# uStar.net
KiCad netlist of a schematic drawn in EAGLE
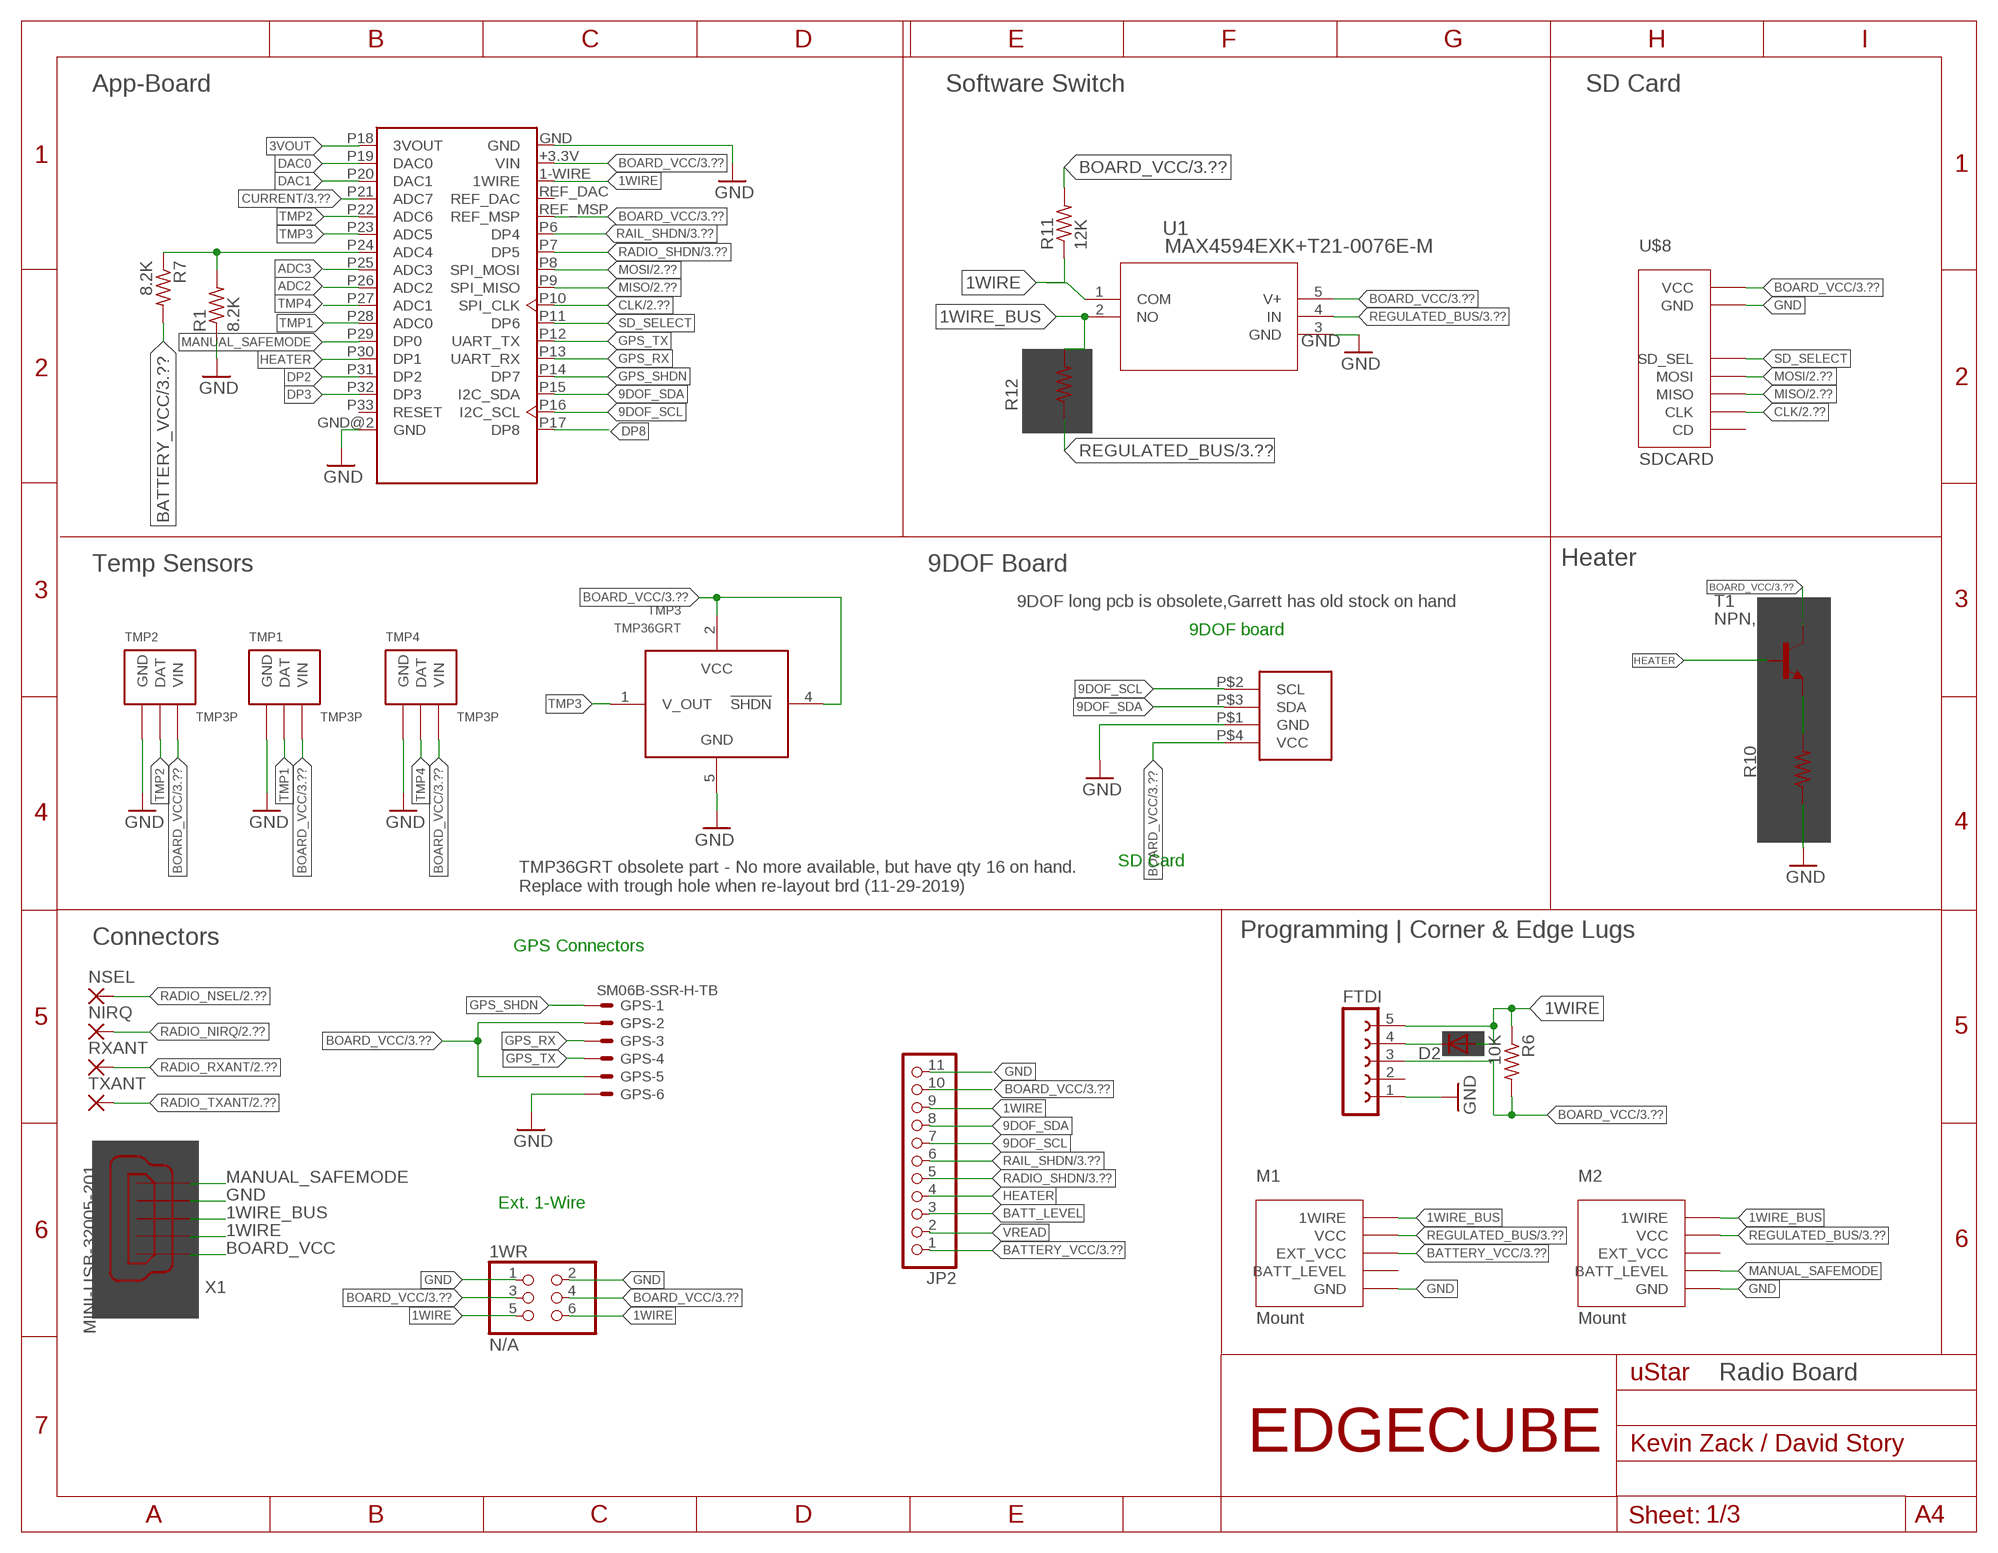
[diagram p0: schematic, sheet 1]
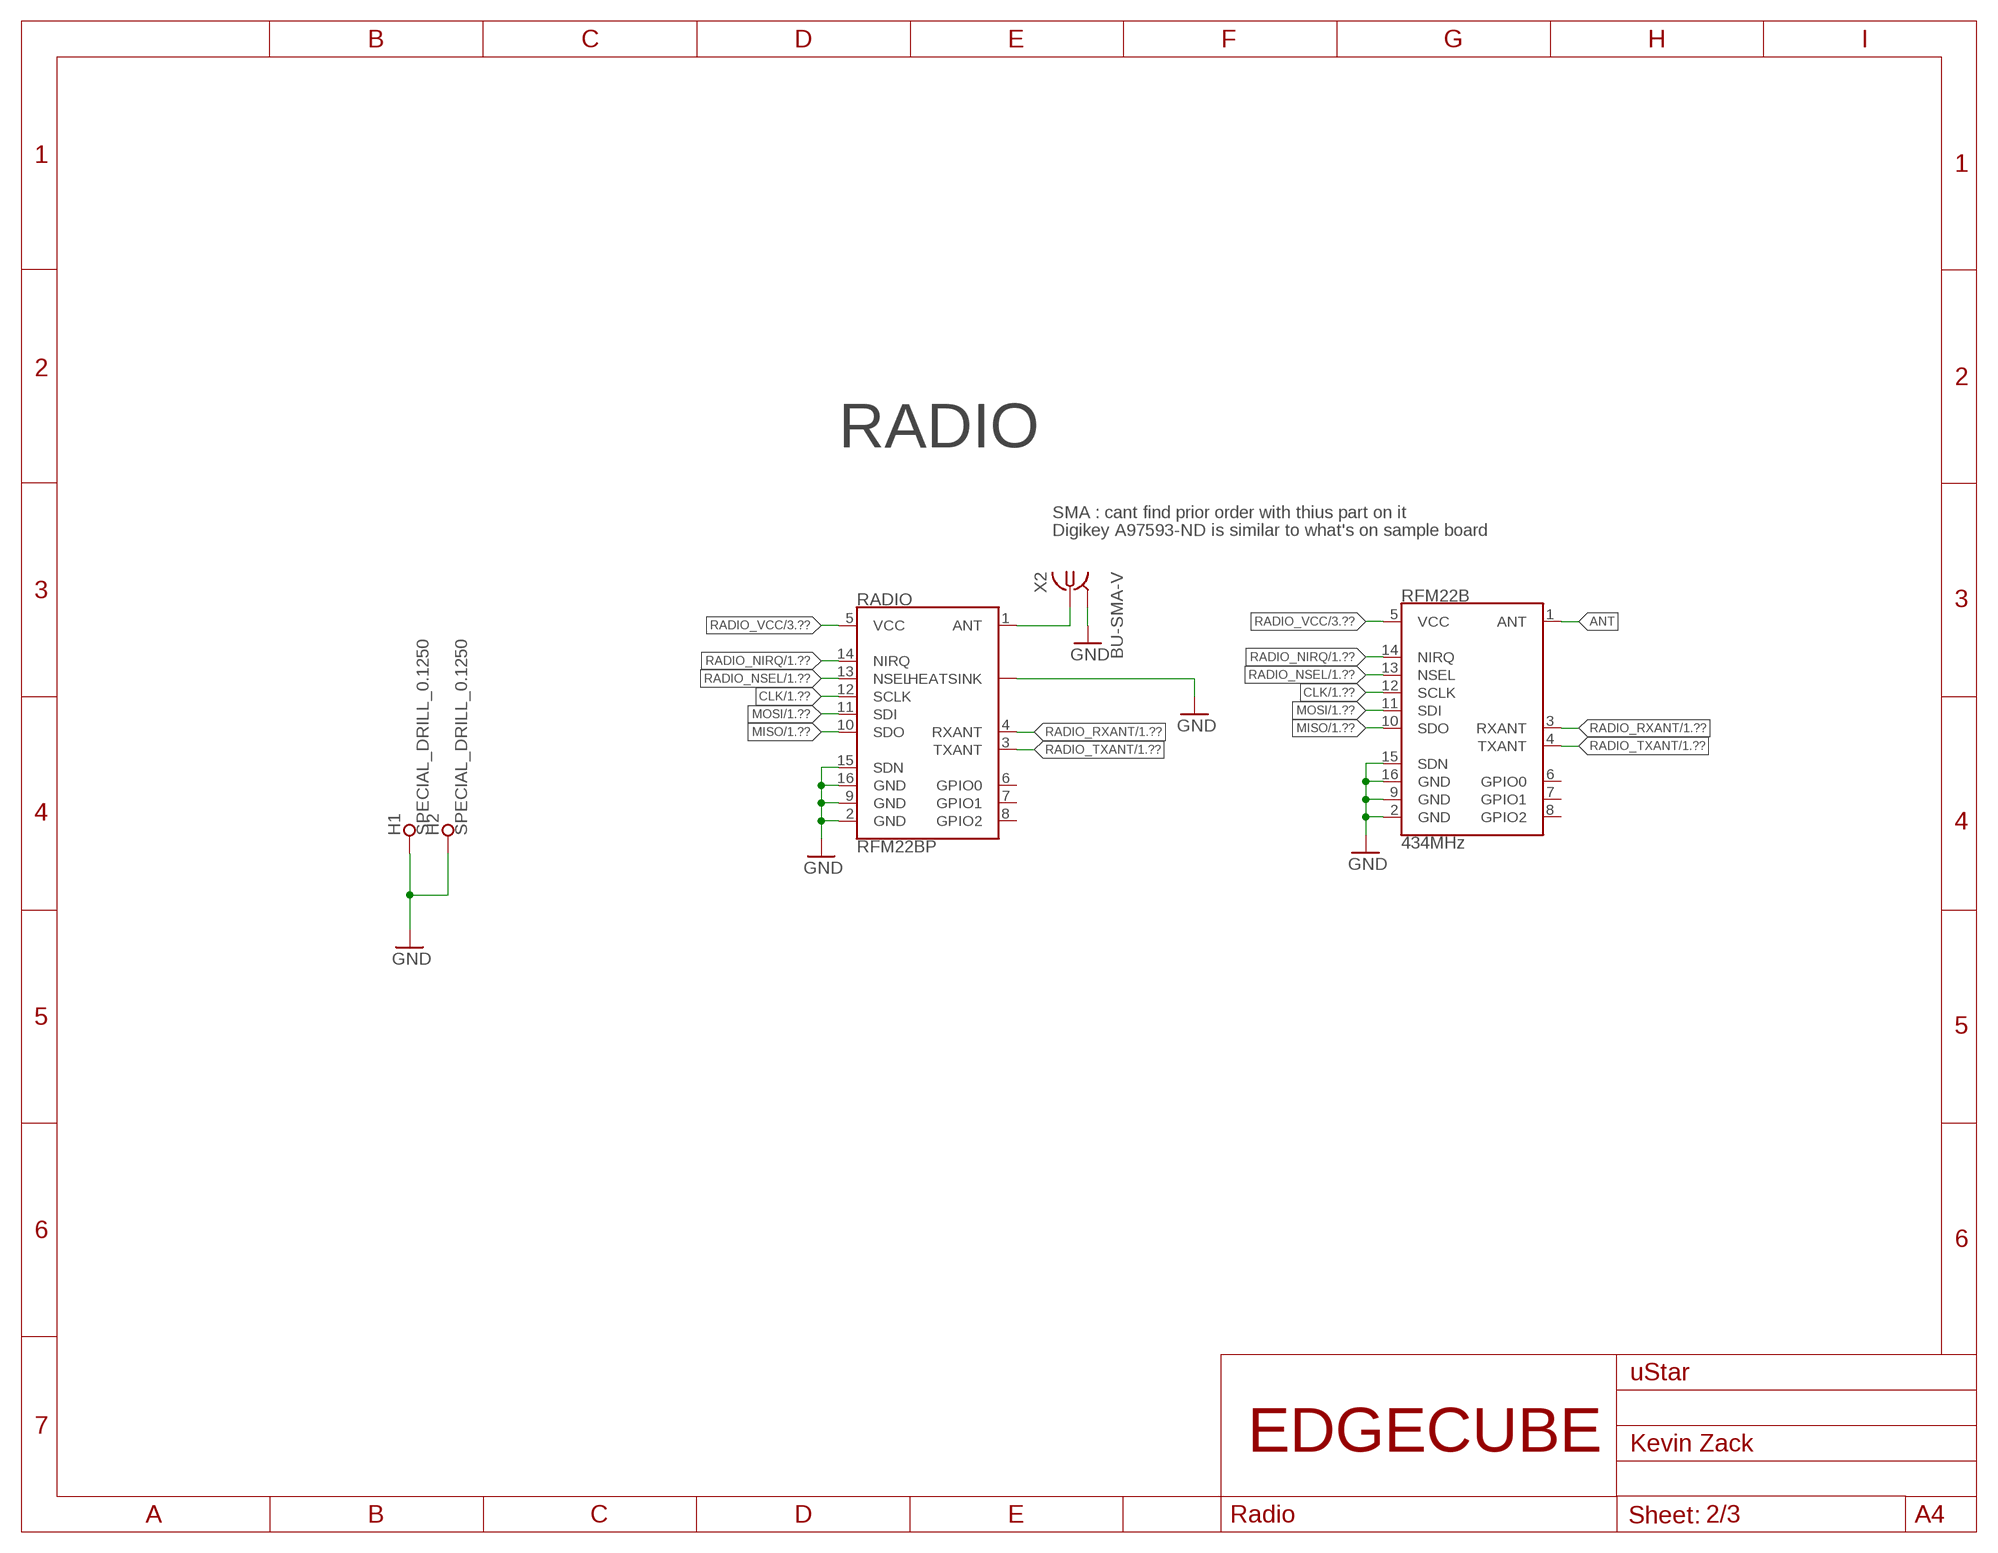
[diagram p1: schematic, sheet 2]
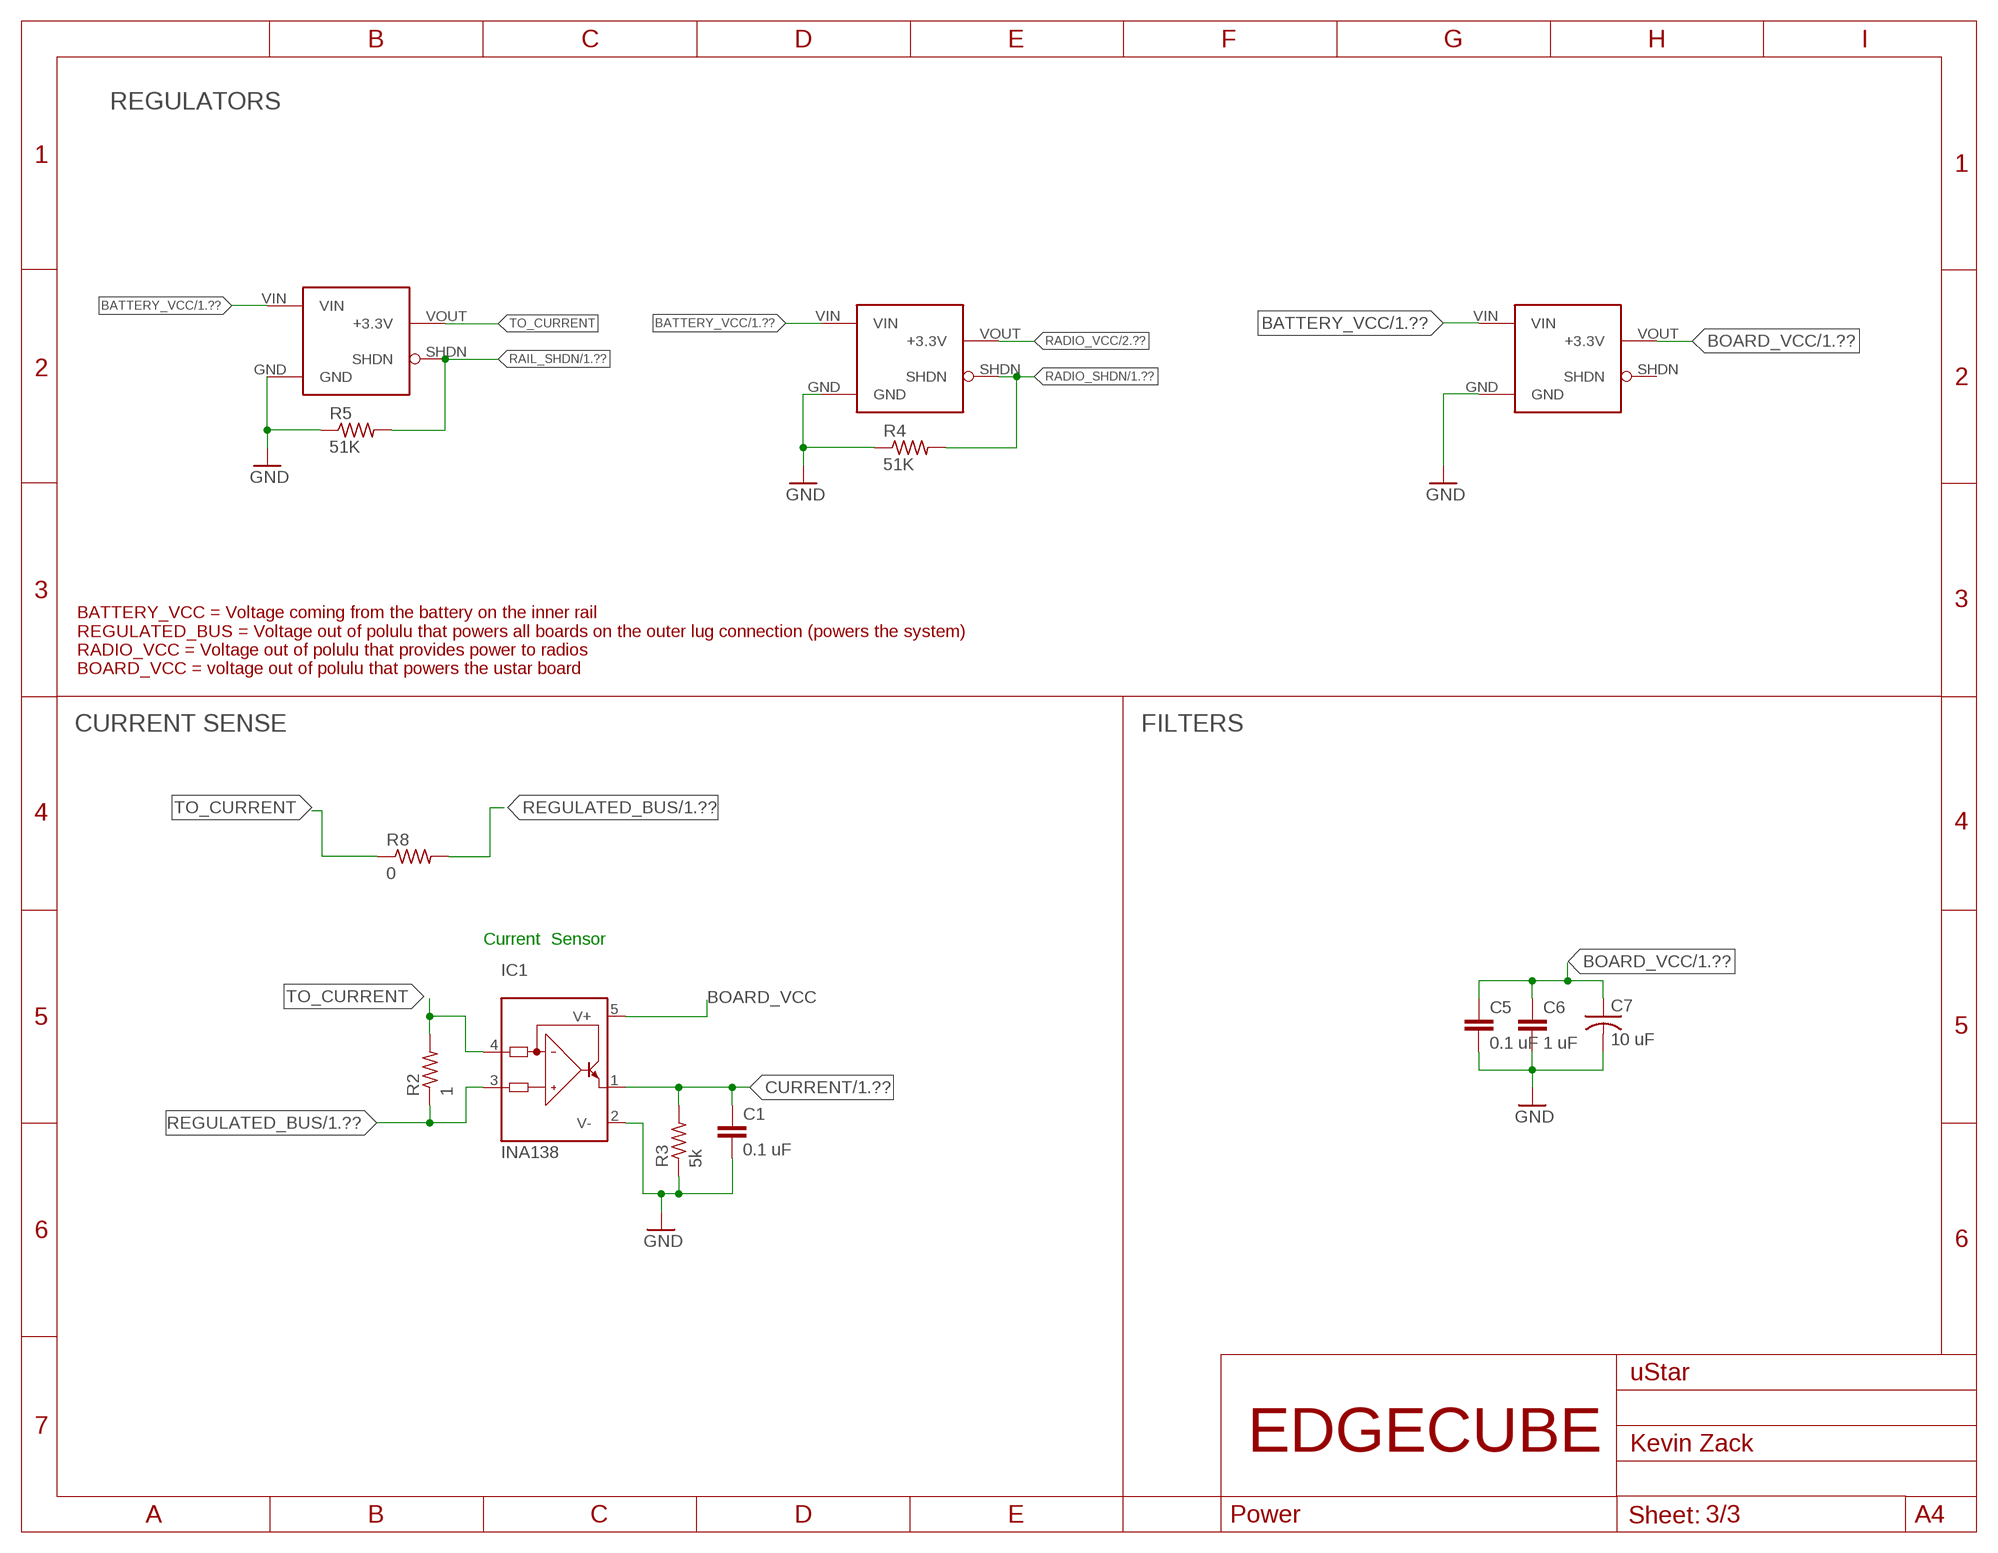
[diagram p2: schematic, sheet 3]

(export (version "E")
  (design (tool "Eeschema 10.0.6"))
  (components
    (comp (ref "C1")
      (value "0.1 uF")
      (footprint "eagle-import:C0603")
      (fields (field (name "MANUFACTURER") "AVX Corperation") (field (name "VOLTAGE") "50 V"))
      (libsource (lib "eagle-import") (part "CAP-0603-0.1UF"))
    )
    (comp (ref "C5")
      (value "0.1 uF")
      (footprint "eagle-import:C0603")
      (fields (field (name "MANUFACTURER") "AVX Corperation") (field (name "VOLTAGE") "50 V"))
      (libsource (lib "eagle-import") (part "CAP-0603-0.1UF"))
    )
    (comp (ref "C6")
      (value "1 uF")
      (footprint "eagle-import:C0603")
      (fields (field (name "MANUFACTURER") "Taiyo Yuden") (field (name "VOLTAGE") "25 V"))
      (libsource (lib "eagle-import") (part "CAP-0603-1UF"))
    )
    (comp (ref "C7")
      (value "10 uF")
      (footprint "eagle-import:C0805_POL")
      (fields (field (name "VOLTAGE") "10 V"))
      (libsource (lib "eagle-import") (part "CAP-0805-10UF-TANT"))
    )
    (comp (ref "IC1")
      (value "INA138")
      (footprint "eagle-import:SOT23-5")
      (fields (field (name "MF") "TEXAS INSTRUMENTS") (field (name "MPN") "INA138NA/250"))
      (libsource (lib "eagle-import") (part "INA138"))
    )
    (comp (ref "R2")
      (value "1")
      (footprint "eagle-import:R0603")
      (libsource (lib "eagle-import") (part "resistor_348_R-US_R0603"))
    )
    (comp (ref "R3")
      (value "5k")
      (footprint "eagle-import:R0603")
      (libsource (lib "eagle-import") (part "resistor_348_R-US_R0603"))
    )
    (comp (ref "R4")
      (value "51K")
      (footprint "eagle-import:R0603")
      (fields (field (name "MANUFACTURER") "Vishay Dale") (field (name "POWER") "0.1W"))
      (libsource (lib "eagle-import") (part "RES-0603-51K"))
    )
    (comp (ref "R5")
      (value "51K")
      (footprint "eagle-import:R0603")
      (fields (field (name "MANUFACTURER") "Vishay Dale") (field (name "POWER") "0.1W"))
      (libsource (lib "eagle-import") (part "RES-0603-51K"))
    )
    (comp (ref "R8")
      (value "0")
      (footprint "eagle-import:R1210W")
      (libsource (lib "eagle-import") (part "R-US_R1210W"))
    )
    (comp (ref "VR1")
      (value "S7V8F3_VOLT_REG-3V3_1AHORZ-DOWN")
      (footprint "eagle-import:S7V_DOWN")
      (libsource (lib "eagle-import") (part "S7V8F3_VOLT_REG-3V3_1AHORZ-DOWN"))
    )
    (comp (ref "VR2")
      (value "S7V8F3_VOLT_REG-3V3_1AHORZ-DOWN")
      (footprint "eagle-import:S7V_DOWN")
      (libsource (lib "eagle-import") (part "S7V8F3_VOLT_REG-3V3_1AHORZ-DOWN"))
    )
    (comp (ref "VR3")
      (value "S7V8F3_VOLT_REG-3V3_1AHORZ-DOWN")
      (footprint "eagle-import:S7V_DOWN")
      (libsource (lib "eagle-import") (part "S7V8F3_VOLT_REG-3V3_1AHORZ-DOWN"))
    )
    (comp (ref "1WR")
      (value "N/A")
      (footprint "eagle-import:2X03")
      (libsource (lib "eagle-import") (part "PINHD-2X3"))
    )
    (comp (ref "D2")
      (value "D-B260A")
      (footprint "eagle-import:SMA-DO214AC")
      (fields (field (name "MANUFACTURER") "Diodes Incorporated") (field (name "VOLTAGE") "60V"))
      (libsource (lib "eagle-import") (part "D-B260A"))
    )
    (comp (ref "FTDI")
      (value "FE05-1")
      (footprint "eagle-import:FE05-1")
      (libsource (lib "eagle-import") (part "FE05-1"))
    )
    (comp (ref "GPS")
      (value "SM06B-SSR-H-TB")
      (footprint "eagle-import:SM06B-SSR-H-TB")
      (libsource (lib "eagle-import") (part "SM06B-SSR-H-TB"))
    )
    (comp (ref "JP2")
      (value "PINHD-1X11")
      (footprint "eagle-import:1X11")
      (libsource (lib "eagle-import") (part "PINHD-1X11"))
    )
    (comp (ref "M1")
      (value "Mount")
      (footprint "eagle-import:4X8MOUNT")
      (libsource (lib "eagle-import") (part "4X8MOUNT"))
    )
    (comp (ref "M2")
      (value "Mount")
      (footprint "eagle-import:4X8MOUNT")
      (libsource (lib "eagle-import") (part "4X8MOUNT"))
    )
    (comp (ref "NIRQ")
      (value "1,6/0,9")
      (footprint "eagle-import:1,6_0,9")
      (libsource (lib "eagle-import") (part "1,6/0,9"))
    )
    (comp (ref "NSEL")
      (value "1,6/0,9")
      (footprint "eagle-import:1,6_0,9")
      (libsource (lib "eagle-import") (part "1,6/0,9"))
    )
    (comp (ref "PCB1")
      (value "9DOF")
      (footprint "eagle-import:9DOF")
      (libsource (lib "eagle-import") (part "9DOF"))
    )
    (comp (ref "R1")
      (value "8.2K")
      (footprint "eagle-import:R0805")
      (libsource (lib "eagle-import") (part "resistor_348_R-US_R0805"))
    )
    (comp (ref "R6")
      (value "10K")
      (footprint "eagle-import:R0603")
      (fields (field (name "MANUFACTURER") "Vishay Dale") (field (name "POWER") "0.1W"))
      (libsource (lib "eagle-import") (part "RES-0603-10K"))
    )
    (comp (ref "R7")
      (value "8.2K")
      (footprint "eagle-import:R0805")
      (libsource (lib "eagle-import") (part "resistor_348_R-US_R0805"))
    )
    (comp (ref "R10")
      (value "22")
      (footprint "eagle-import:0207_7")
      (libsource (lib "eagle-import") (part "R-US_0207/7"))
    )
    (comp (ref "R11")
      (value "12K")
      (footprint "eagle-import:R0805")
      (libsource (lib "eagle-import") (part "R-US_R0805"))
    )
    (comp (ref "R12")
      (value "NP")
      (footprint "eagle-import:R0805")
      (libsource (lib "eagle-import") (part "R-US_R0805"))
    )
    (comp (ref "RXANT")
      (value "1,6/0,9")
      (footprint "eagle-import:1,6_0,9")
      (libsource (lib "eagle-import") (part "1,6/0,9"))
    )
    (comp (ref "T1")
      (value "NPN, 0.25A")
      (footprint "eagle-import:TO92-EBC-OVAL")
      (libsource (lib "eagle-import") (part "2N2222"))
    )
    (comp (ref "TMP1")
      (value "TMP3P")
      (footprint "eagle-import:TMP3P")
      (libsource (lib "eagle-import") (part "TMP3P"))
    )
    (comp (ref "TMP2")
      (value "TMP3P")
      (footprint "eagle-import:TMP3P")
      (libsource (lib "eagle-import") (part "TMP3P"))
    )
    (comp (ref "TMP3")
      (value "TMP36GRT")
      (footprint "eagle-import:SOT-23-5")
      (fields
        (field (name "MANUFACTURER") "Analog Devices Inc.")
        (field (name "VOLTAGE") "2.7V-5.5V")
        (field (name "DIGIKEY") "obsolete")
      )
      (libsource (lib "eagle-import") (part "TMP36GRT"))
    )
    (comp (ref "TMP4")
      (value "TMP3P")
      (footprint "eagle-import:TMP3P")
      (libsource (lib "eagle-import") (part "TMP3P"))
    )
    (comp (ref "TXANT")
      (value "1,6/0,9")
      (footprint "eagle-import:1,6_0,9")
      (libsource (lib "eagle-import") (part "1,6/0,9"))
    )
    (comp (ref "U$1")
      (value "App-Board 1.2/1.3")
      (footprint "eagle-import:APPCORE_RECEIVER")
      (libsource (lib "eagle-import") (part "APP_CORE"))
    )
    (comp (ref "U$8")
      (value "SDCARD")
      (footprint "eagle-import:SDCARD")
      (libsource (lib "eagle-import") (part "SDCARD"))
    )
    (comp (ref "U1")
      (value "MAX4594EXK+T21-0076E-M")
      (footprint "eagle-import:21-0076E-M")
      (fields (field (name "MANUFACTURER_PART_NUMBER") "MAX4594EXK+T"))
      (libsource (lib "eagle-import") (part "MAX4594EXK+T21-0076E-M"))
    )
    (comp (ref "X1")
      (value "MINI-USB-32005-201")
      (footprint "eagle-import:32005-201")
      (libsource (lib "eagle-import") (part "MINI-USB-32005-201"))
    )
    (comp (ref "H1")
      (value "SPECIAL_DRILL_0.1250")
      (footprint "eagle-import:PAD_0.1250")
      (libsource (lib "eagle-import") (part "SPECIAL_DRILL_0.1250"))
    )
    (comp (ref "H2")
      (value "SPECIAL_DRILL_0.1250")
      (footprint "eagle-import:PAD_0.1250")
      (libsource (lib "eagle-import") (part "SPECIAL_DRILL_0.1250"))
    )
    (comp (ref "RADIO")
      (value "RFM22BP")
      (footprint "eagle-import:RFM22BP")
      (fields (field (name "MANUFACTURER") "HOPERF Electronic"))
      (libsource (lib "eagle-import") (part "RFM22BP"))
    )
    (comp (ref "RFM22B")
      (value "434MHz")
      (footprint "eagle-import:RFM22-XXX-S2")
      (libsource (lib "eagle-import") (part "RFM22434MHZ"))
    )
    (comp (ref "X2")
      (value "BU-SMA-V")
      (footprint "eagle-import:BU-SMA-V")
      (libsource (lib "eagle-import") (part "BU-SMA-V"))
    )
  )
  (nets
    (net (code "1") (name "1WIRE") (class "Default")
      (node (ref "1WR") (pin "5") (pinfunction "5_5") (pintype "passive"))
      (node (ref "1WR") (pin "6") (pinfunction "6_6") (pintype "passive"))
      (node (ref "D2") (pin "A") (pinfunction "A_A") (pintype "passive"))
      (node (ref "FTDI") (pin "5") (pinfunction "5_5") (pintype "passive"))
      (node (ref "JP2") (pin "9") (pinfunction "9_9") (pintype "passive"))
      (node (ref "R11") (pin "1") (pinfunction "1_1") (pintype "passive"))
      (node (ref "R6") (pin "1") (pinfunction "1_1") (pintype "passive"))
      (node (ref "U$1") (pin "1-WIRE") (pinfunction "1WIRE_1-WIRE") (pintype "bidirectional"))
      (node (ref "U1") (pin "1") (pinfunction "COM_1") (pintype "passive"))
      (node (ref "X1") (pin "2") (pinfunction "2_2") (pintype "passive"))
    )
    (net (code "2") (name "1WIRE_BUS") (class "Default")
      (node (ref "M1") (pin "P$2") (pinfunction "1WIRE_P$2") (pintype "bidirectional"))
      (node (ref "M1") (pin "P$5") (pinfunction "1WIRE_P$5") (pintype "bidirectional"))
      (node (ref "M2") (pin "P$2") (pinfunction "1WIRE_P$2") (pintype "bidirectional"))
      (node (ref "M2") (pin "P$5") (pinfunction "1WIRE_P$5") (pintype "bidirectional"))
      (node (ref "R12") (pin "2") (pinfunction "2_2") (pintype "passive"))
      (node (ref "U1") (pin "2") (pinfunction "NO_2") (pintype "passive"))
      (node (ref "X1") (pin "3") (pinfunction "3_3") (pintype "passive"))
    )
    (net (code "3") (name "3VOUT") (class "Default")
      (node (ref "U$1") (pin "P18") (pinfunction "3VOUT_P18") (pintype "output"))
    )
    (net (code "4") (name "9DOF_SCL") (class "Default")
      (node (ref "JP2") (pin "7") (pinfunction "7_7") (pintype "passive"))
      (node (ref "PCB1") (pin "P$2") (pinfunction "SCL_P$2") (pintype "bidirectional"))
      (node (ref "U$1") (pin "P16") (pinfunction "I2C_SCL_P16") (pintype "bidirectional"))
    )
    (net (code "5") (name "9DOF_SDA") (class "Default")
      (node (ref "JP2") (pin "8") (pinfunction "8_8") (pintype "passive"))
      (node (ref "PCB1") (pin "P$3") (pinfunction "SDA_P$3") (pintype "bidirectional"))
      (node (ref "U$1") (pin "P15") (pinfunction "I2C_SDA_P15") (pintype "bidirectional"))
    )
    (net (code "6") (name "ADC2") (class "Default")
      (node (ref "U$1") (pin "P26") (pinfunction "ADC2_P26") (pintype "input"))
    )
    (net (code "7") (name "ADC3") (class "Default")
      (node (ref "U$1") (pin "P25") (pinfunction "ADC3_P25") (pintype "input"))
    )
    (net (code "8") (name "ANT") (class "Default")
      (node (ref "RADIO") (pin "1") (pinfunction "ANT_1") (pintype "bidirectional"))
      (node (ref "RFM22B") (pin "1") (pinfunction "ANT_1") (pintype "bidirectional"))
      (node (ref "X2") (pin "1") (pinfunction "1_1") (pintype "passive"))
    )
    (net (code "9") (name "BATTERY_VCC") (class "Default")
      (node (ref "JP2") (pin "1") (pinfunction "1_1") (pintype "passive"))
      (node (ref "M1") (pin "P$3") (pinfunction "EXT_VCC_P$3") (pintype "bidirectional"))
      (node (ref "R7") (pin "2") (pinfunction "2_2") (pintype "passive"))
      (node (ref "VR1") (pin "VIN") (pinfunction "VIN_VIN") (pintype "power_in"))
      (node (ref "VR2") (pin "VIN") (pinfunction "VIN_VIN") (pintype "power_in"))
      (node (ref "VR3") (pin "VIN") (pinfunction "VIN_VIN") (pintype "power_in"))
    )
    (net (code "10") (name "BATT_LEVEL") (class "Default")
      (node (ref "JP2") (pin "3") (pinfunction "3_3") (pintype "passive"))
    )
    (net (code "11") (name "BOARD_VCC") (class "Default")
      (node (ref "1WR") (pin "3") (pinfunction "3_3") (pintype "passive"))
      (node (ref "1WR") (pin "4") (pinfunction "4_4") (pintype "passive"))
      (node (ref "C5") (pin "1") (pinfunction "1_1") (pintype "passive"))
      (node (ref "C6") (pin "1") (pinfunction "1_1") (pintype "passive"))
      (node (ref "C7") (pin "2") (pinfunction "1_2") (pintype "passive"))
      (node (ref "FTDI") (pin "3") (pinfunction "3_3") (pintype "passive"))
      (node (ref "GPS") (pin "2") (pinfunction "S_2") (pintype "passive"))
      (node (ref "GPS") (pin "5") (pinfunction "S_5") (pintype "passive"))
      (node (ref "IC1") (pin "5") (pinfunction "V+_5") (pintype "power_in"))
      (node (ref "JP2") (pin "10") (pinfunction "10_10") (pintype "passive"))
      (node (ref "PCB1") (pin "P$4") (pinfunction "VCC_P$4") (pintype "bidirectional"))
      (node (ref "R11") (pin "2") (pinfunction "2_2") (pintype "passive"))
      (node (ref "R6") (pin "2") (pinfunction "2_2") (pintype "passive"))
      (node (ref "T1") (pin "C") (pinfunction "C_C") (pintype "passive"))
      (node (ref "TMP1") (pin "P$3") (pinfunction "VIN_P$3") (pintype "bidirectional"))
      (node (ref "TMP2") (pin "P$3") (pinfunction "VIN_P$3") (pintype "bidirectional"))
      (node (ref "TMP3") (pin "2") (pinfunction "VCC_2") (pintype "power_in"))
      (node (ref "TMP3") (pin "4") (pinfunction "~{SHDN}_4") (pintype "input"))
      (node (ref "TMP4") (pin "P$3") (pinfunction "VIN_P$3") (pintype "bidirectional"))
      (node (ref "U$1") (pin "+3.3V") (pinfunction "VIN_+3.3V") (pintype "power_in"))
      (node (ref "U$1") (pin "REF_MSP") (pinfunction "REF_MSP_REF_MSP") (pintype "input"))
      (node (ref "U$8") (pin "P$3") (pinfunction "VCC_P$3") (pintype "bidirectional"))
      (node (ref "U1") (pin "5") (pinfunction "V+_5") (pintype "power_in"))
      (node (ref "VR3") (pin "VOUT") (pinfunction "+3.3V_VOUT") (pintype "output"))
      (node (ref "X1") (pin "1") (pinfunction "1_1") (pintype "passive"))
    )
    (net (code "12") (name "CLK") (class "Default")
      (node (ref "RADIO") (pin "12") (pinfunction "SCLK_12") (pintype "input"))
      (node (ref "RFM22B") (pin "12") (pinfunction "SCLK_12") (pintype "input"))
      (node (ref "U$1") (pin "P10") (pinfunction "SPI_CLK_P10") (pintype "bidirectional"))
      (node (ref "U$8") (pin "P$4") (pinfunction "CLK_P$4") (pintype "bidirectional"))
    )
    (net (code "13") (name "CURRENT") (class "Default")
      (node (ref "C1") (pin "1") (pinfunction "1_1") (pintype "passive"))
      (node (ref "IC1") (pin "1") (pinfunction "OUT_1") (pintype "output"))
      (node (ref "R3") (pin "2") (pinfunction "2_2") (pintype "passive"))
      (node (ref "U$1") (pin "P21") (pinfunction "ADC7_P21") (pintype "input"))
    )
    (net (code "14") (name "DAC0") (class "Default")
      (node (ref "U$1") (pin "P19") (pinfunction "DAC0_P19") (pintype "bidirectional"))
    )
    (net (code "15") (name "DAC1") (class "Default")
      (node (ref "U$1") (pin "P20") (pinfunction "DAC1_P20") (pintype "bidirectional"))
    )
    (net (code "16") (name "DP2") (class "Default")
      (node (ref "U$1") (pin "P31") (pinfunction "DP2_P31") (pintype "bidirectional"))
    )
    (net (code "17") (name "DP3") (class "Default")
      (node (ref "U$1") (pin "P32") (pinfunction "DP3_P32") (pintype "bidirectional"))
    )
    (net (code "18") (name "DP8") (class "Default")
      (node (ref "U$1") (pin "P17") (pinfunction "DP8_P17") (pintype "bidirectional"))
    )
    (net (code "19") (name "GND") (class "Default")
      (node (ref "1WR") (pin "1") (pinfunction "1_1") (pintype "passive"))
      (node (ref "1WR") (pin "2") (pinfunction "2_2") (pintype "passive"))
      (node (ref "C1") (pin "2") (pinfunction "2_2") (pintype "passive"))
      (node (ref "C5") (pin "2") (pinfunction "2_2") (pintype "passive"))
      (node (ref "C6") (pin "2") (pinfunction "2_2") (pintype "passive"))
      (node (ref "C7") (pin "1") (pinfunction "2_1") (pintype "passive"))
      (node (ref "FTDI") (pin "1") (pinfunction "1_1") (pintype "passive"))
      (node (ref "GPS") (pin "6") (pinfunction "S_6") (pintype "passive"))
      (node (ref "H1") (pin "1") (pinfunction "1_1") (pintype "passive"))
      (node (ref "H2") (pin "1") (pinfunction "1_1") (pintype "passive"))
      (node (ref "IC1") (pin "2") (pinfunction "V-_2") (pintype "power_in"))
      (node (ref "JP2") (pin "11") (pinfunction "11_11") (pintype "passive"))
      (node (ref "M1") (pin "P$1") (pinfunction "GND_P$1") (pintype "bidirectional"))
      (node (ref "M1") (pin "P$8") (pinfunction "GND_P$8") (pintype "bidirectional"))
      (node (ref "M2") (pin "P$1") (pinfunction "GND_P$1") (pintype "bidirectional"))
      (node (ref "M2") (pin "P$8") (pinfunction "GND_P$8") (pintype "bidirectional"))
      (node (ref "PCB1") (pin "P$1") (pinfunction "GND_P$1") (pintype "bidirectional"))
      (node (ref "R1") (pin "1") (pinfunction "1_1") (pintype "passive"))
      (node (ref "R10") (pin "1") (pinfunction "1_1") (pintype "passive"))
      (node (ref "R3") (pin "1") (pinfunction "1_1") (pintype "passive"))
      (node (ref "R4") (pin "1") (pinfunction "1_1") (pintype "passive"))
      (node (ref "R5") (pin "1") (pinfunction "1_1") (pintype "passive"))
      (node (ref "RADIO") (pin "15") (pinfunction "SDN_15") (pintype "input"))
      (node (ref "RADIO") (pin "16") (pinfunction "GND_16") (pintype "power_in"))
      (node (ref "RADIO") (pin "2") (pinfunction "GND_2") (pintype "power_in"))
      (node (ref "RADIO") (pin "9") (pinfunction "GND_9") (pintype "power_in"))
      (node (ref "RADIO") (pin "P$1") (pinfunction "HEATSINK_P$1") (pintype "bidirectional"))
      (node (ref "RFM22B") (pin "15") (pinfunction "SDN_15") (pintype "input"))
      (node (ref "RFM22B") (pin "16") (pinfunction "GND_16") (pintype "power_in"))
      (node (ref "RFM22B") (pin "2") (pinfunction "GND_2") (pintype "power_in"))
      (node (ref "RFM22B") (pin "9") (pinfunction "GND_9") (pintype "power_in"))
      (node (ref "TMP1") (pin "P$1") (pinfunction "GND_P$1") (pintype "bidirectional"))
      (node (ref "TMP2") (pin "P$1") (pinfunction "GND_P$1") (pintype "bidirectional"))
      (node (ref "TMP3") (pin "5") (pinfunction "GND_5") (pintype "power_in"))
      (node (ref "TMP4") (pin "P$1") (pinfunction "GND_P$1") (pintype "bidirectional"))
      (node (ref "U$1") (pin "GND") (pinfunction "GND_GND") (pintype "power_in"))
      (node (ref "U$1") (pin "GND@2") (pinfunction "GND_GND@2") (pintype "power_in"))
      (node (ref "U$8") (pin "P$5") (pinfunction "GND_P$5") (pintype "bidirectional"))
      (node (ref "U1") (pin "3") (pinfunction "GND_3") (pintype "power_in"))
      (node (ref "VR1") (pin "GND") (pinfunction "GND_GND") (pintype "power_in"))
      (node (ref "VR2") (pin "GND") (pinfunction "GND_GND") (pintype "power_in"))
      (node (ref "VR3") (pin "GND") (pinfunction "GND_GND") (pintype "power_in"))
      (node (ref "X1") (pin "4") (pinfunction "4_4") (pintype "passive"))
      (node (ref "X2") (pin "2") (pinfunction "2_2") (pintype "passive"))
      (node (ref "X2") (pin "3") (pinfunction "2_3") (pintype "passive"))
      (node (ref "X2") (pin "4") (pinfunction "2_4") (pintype "passive"))
      (node (ref "X2") (pin "5") (pinfunction "2_5") (pintype "passive"))
    )
    (net (code "20") (name "GPS_RX") (class "Default")
      (node (ref "GPS") (pin "3") (pinfunction "S_3") (pintype "passive"))
      (node (ref "U$1") (pin "P13") (pinfunction "UART_RX_P13") (pintype "input"))
    )
    (net (code "21") (name "GPS_SHDN") (class "Default")
      (node (ref "GPS") (pin "1") (pinfunction "S_1") (pintype "passive"))
      (node (ref "U$1") (pin "P14") (pinfunction "DP7_P14") (pintype "bidirectional"))
    )
    (net (code "22") (name "GPS_TX") (class "Default")
      (node (ref "GPS") (pin "4") (pinfunction "S_4") (pintype "passive"))
      (node (ref "U$1") (pin "P12") (pinfunction "UART_TX_P12") (pintype "output"))
    )
    (net (code "23") (name "HEATER") (class "Default")
      (node (ref "JP2") (pin "4") (pinfunction "4_4") (pintype "passive"))
      (node (ref "T1") (pin "B") (pinfunction "B_B") (pintype "passive"))
      (node (ref "U$1") (pin "P30") (pinfunction "DP1_P30") (pintype "bidirectional"))
    )
    (net (code "24") (name "MANUAL_SAFEMODE") (class "Default")
      (node (ref "M2") (pin "P$6") (pinfunction "BATT_LEVEL_P$6") (pintype "bidirectional"))
      (node (ref "U$1") (pin "P29") (pinfunction "DP0_P29") (pintype "bidirectional"))
      (node (ref "X1") (pin "5") (pinfunction "5_5") (pintype "passive"))
    )
    (net (code "25") (name "MISO") (class "Default")
      (node (ref "RADIO") (pin "10") (pinfunction "SDO_10") (pintype "output"))
      (node (ref "RFM22B") (pin "10") (pinfunction "SDO_10") (pintype "output"))
      (node (ref "U$1") (pin "P9") (pinfunction "SPI_MISO_P9") (pintype "bidirectional"))
      (node (ref "U$8") (pin "P$6") (pinfunction "MISO_P$6") (pintype "bidirectional"))
    )
    (net (code "26") (name "MOSI") (class "Default")
      (node (ref "RADIO") (pin "11") (pinfunction "SDI_11") (pintype "input"))
      (node (ref "RFM22B") (pin "11") (pinfunction "SDI_11") (pintype "input"))
      (node (ref "U$1") (pin "P8") (pinfunction "SPI_MOSI_P8") (pintype "bidirectional"))
      (node (ref "U$8") (pin "P$2") (pinfunction "MOSI_P$2") (pintype "bidirectional"))
    )
    (net (code "27") (name "Net-(D2-C)") (class "Default")
      (node (ref "D2") (pin "K") (pinfunction "C_K") (pintype "passive"))
      (node (ref "FTDI") (pin "4") (pinfunction "4_4") (pintype "passive"))
    )
    (net (code "28") (name "Net-(R10-Pad2)") (class "Default")
      (node (ref "R10") (pin "2") (pinfunction "2_2") (pintype "passive"))
      (node (ref "T1") (pin "E") (pinfunction "E_E") (pintype "passive"))
    )
    (net (code "29") (name "Net-(U$1-ADC4)") (class "Default")
      (node (ref "R1") (pin "2") (pinfunction "2_2") (pintype "passive"))
      (node (ref "R7") (pin "1") (pinfunction "1_1") (pintype "passive"))
      (node (ref "U$1") (pin "P24") (pinfunction "ADC4_P24") (pintype "input"))
    )
    (net (code "30") (name "RADIO_NIRQ") (class "Default")
      (node (ref "NIRQ") (pin "1") (pinfunction "P_1") (pintype "passive"))
      (node (ref "RADIO") (pin "14") (pinfunction "NIRQ_14") (pintype "output"))
      (node (ref "RFM22B") (pin "14") (pinfunction "NIRQ_14") (pintype "output"))
    )
    (net (code "31") (name "RADIO_NSEL") (class "Default")
      (node (ref "NSEL") (pin "1") (pinfunction "P_1") (pintype "passive"))
      (node (ref "RADIO") (pin "13") (pinfunction "NSEL_13") (pintype "input"))
      (node (ref "RFM22B") (pin "13") (pinfunction "NSEL_13") (pintype "input"))
    )
    (net (code "32") (name "RADIO_RXANT") (class "Default")
      (node (ref "RADIO") (pin "4") (pinfunction "RXANT_4") (pintype "input"))
      (node (ref "RFM22B") (pin "3") (pinfunction "RXANT_3") (pintype "input"))
      (node (ref "RXANT") (pin "1") (pinfunction "P_1") (pintype "passive"))
    )
    (net (code "33") (name "RADIO_SHDN") (class "Default")
      (node (ref "JP2") (pin "5") (pinfunction "5_5") (pintype "passive"))
      (node (ref "R4") (pin "2") (pinfunction "2_2") (pintype "passive"))
      (node (ref "U$1") (pin "P7") (pinfunction "DP5_P7") (pintype "bidirectional"))
      (node (ref "VR2") (pin "SHDN") (pinfunction "SHDN_SHDN") (pintype "input"))
    )
    (net (code "34") (name "RADIO_TXANT") (class "Default")
      (node (ref "RADIO") (pin "3") (pinfunction "TXANT_3") (pintype "input"))
      (node (ref "RFM22B") (pin "4") (pinfunction "TXANT_4") (pintype "input"))
      (node (ref "TXANT") (pin "1") (pinfunction "P_1") (pintype "passive"))
    )
    (net (code "35") (name "RADIO_VCC") (class "Default")
      (node (ref "RADIO") (pin "5") (pinfunction "VCC_5") (pintype "bidirectional"))
      (node (ref "RFM22B") (pin "5") (pinfunction "VCC_5") (pintype "bidirectional"))
      (node (ref "VR2") (pin "VOUT") (pinfunction "+3.3V_VOUT") (pintype "output"))
    )
    (net (code "36") (name "RAIL_SHDN") (class "Default")
      (node (ref "JP2") (pin "6") (pinfunction "6_6") (pintype "passive"))
      (node (ref "R5") (pin "2") (pinfunction "2_2") (pintype "passive"))
      (node (ref "U$1") (pin "P6") (pinfunction "DP4_P6") (pintype "bidirectional"))
      (node (ref "VR1") (pin "SHDN") (pinfunction "SHDN_SHDN") (pintype "input"))
    )
    (net (code "37") (name "REGULATED_BUS") (class "Default")
      (node (ref "IC1") (pin "3") (pinfunction "IN+_3") (pintype "input"))
      (node (ref "M1") (pin "P$4") (pinfunction "VCC_P$4") (pintype "bidirectional"))
      (node (ref "M1") (pin "P$7") (pinfunction "VCC_P$7") (pintype "bidirectional"))
      (node (ref "M2") (pin "P$4") (pinfunction "VCC_P$4") (pintype "bidirectional"))
      (node (ref "M2") (pin "P$7") (pinfunction "VCC_P$7") (pintype "bidirectional"))
      (node (ref "R12") (pin "1") (pinfunction "1_1") (pintype "passive"))
      (node (ref "R2") (pin "1") (pinfunction "1_1") (pintype "passive"))
      (node (ref "R8") (pin "2") (pinfunction "2_2") (pintype "passive"))
      (node (ref "U1") (pin "4") (pinfunction "IN_4") (pintype "input"))
    )
    (net (code "38") (name "SD_SELECT") (class "Default")
      (node (ref "U$1") (pin "P11") (pinfunction "DP6_P11") (pintype "bidirectional"))
      (node (ref "U$8") (pin "P$1") (pinfunction "SD_SEL_P$1") (pintype "bidirectional"))
    )
    (net (code "39") (name "TMP1") (class "Default")
      (node (ref "TMP1") (pin "P$2") (pinfunction "DAT_P$2") (pintype "bidirectional"))
      (node (ref "U$1") (pin "P28") (pinfunction "ADC0_P28") (pintype "input"))
    )
    (net (code "40") (name "TMP2") (class "Default")
      (node (ref "TMP2") (pin "P$2") (pinfunction "DAT_P$2") (pintype "bidirectional"))
      (node (ref "U$1") (pin "P22") (pinfunction "ADC6_P22") (pintype "input"))
    )
    (net (code "41") (name "TMP3") (class "Default")
      (node (ref "TMP3") (pin "1") (pinfunction "V_OUT_1") (pintype "output"))
      (node (ref "U$1") (pin "P23") (pinfunction "ADC5_P23") (pintype "input"))
    )
    (net (code "42") (name "TMP4") (class "Default")
      (node (ref "TMP4") (pin "P$2") (pinfunction "DAT_P$2") (pintype "bidirectional"))
      (node (ref "U$1") (pin "P27") (pinfunction "ADC1_P27") (pintype "input"))
    )
    (net (code "43") (name "TO_CURRENT") (class "Default")
      (node (ref "IC1") (pin "4") (pinfunction "IN-_4") (pintype "input"))
      (node (ref "R2") (pin "2") (pinfunction "2_2") (pintype "passive"))
      (node (ref "R8") (pin "1") (pinfunction "1_1") (pintype "passive"))
      (node (ref "VR1") (pin "VOUT") (pinfunction "+3.3V_VOUT") (pintype "output"))
    )
    (net (code "44") (name "VREAD") (class "Default")
      (node (ref "JP2") (pin "2") (pinfunction "2_2") (pintype "passive"))
    )
    (net (code "45") (name "unconnected-(FTDI-Pad2)") (class "Default")
      (node (ref "FTDI") (pin "2") (pinfunction "2_2") (pintype "passive"))
    )
    (net (code "46") (name "unconnected-(M1-BATT_LEVEL-PadP$6)") (class "Default")
      (node (ref "M1") (pin "P$6") (pinfunction "BATT_LEVEL_P$6") (pintype "bidirectional"))
    )
    (net (code "47") (name "unconnected-(M2-EXT_VCC-PadP$3)") (class "Default")
      (node (ref "M2") (pin "P$3") (pinfunction "EXT_VCC_P$3") (pintype "bidirectional"))
    )
    (net (code "48") (name "unconnected-(RADIO-GPIO0-Pad6)") (class "Default")
      (node (ref "RADIO") (pin "6") (pinfunction "GPIO0_6") (pintype "bidirectional"))
    )
    (net (code "49") (name "unconnected-(RADIO-GPIO1-Pad7)") (class "Default")
      (node (ref "RADIO") (pin "7") (pinfunction "GPIO1_7") (pintype "bidirectional"))
    )
    (net (code "50") (name "unconnected-(RADIO-GPIO2-Pad8)") (class "Default")
      (node (ref "RADIO") (pin "8") (pinfunction "GPIO2_8") (pintype "bidirectional"))
    )
    (net (code "51") (name "unconnected-(RFM22B-GPIO0-Pad6)") (class "Default")
      (node (ref "RFM22B") (pin "6") (pinfunction "GPIO0_6") (pintype "bidirectional"))
    )
    (net (code "52") (name "unconnected-(RFM22B-GPIO1-Pad7)") (class "Default")
      (node (ref "RFM22B") (pin "7") (pinfunction "GPIO1_7") (pintype "bidirectional"))
    )
    (net (code "53") (name "unconnected-(RFM22B-GPIO2-Pad8)") (class "Default")
      (node (ref "RFM22B") (pin "8") (pinfunction "GPIO2_8") (pintype "bidirectional"))
    )
    (net (code "54") (name "unconnected-(U$1-PadREF_DAC)") (class "Default")
      (node (ref "U$1") (pin "REF_DAC") (pinfunction "REF_DAC_REF_DAC") (pintype "input"))
    )
    (net (code "55") (name "unconnected-(U$1-RESET-PadP33)") (class "Default")
      (node (ref "U$1") (pin "P33") (pinfunction "RESET_P33") (pintype "bidirectional"))
    )
    (net (code "56") (name "unconnected-(U$8-CD-PadP$7)") (class "Default")
      (node (ref "U$8") (pin "P$7") (pinfunction "CD_P$7") (pintype "bidirectional"))
    )
    (net (code "57") (name "unconnected-(VR3-PadSHDN)") (class "Default")
      (node (ref "VR3") (pin "SHDN") (pinfunction "SHDN_SHDN") (pintype "input"))
    )
  )
)
